# SCH_LeftHalf_2022-04-16.net
KiCad netlist of a schematic drawn in EasyEDA
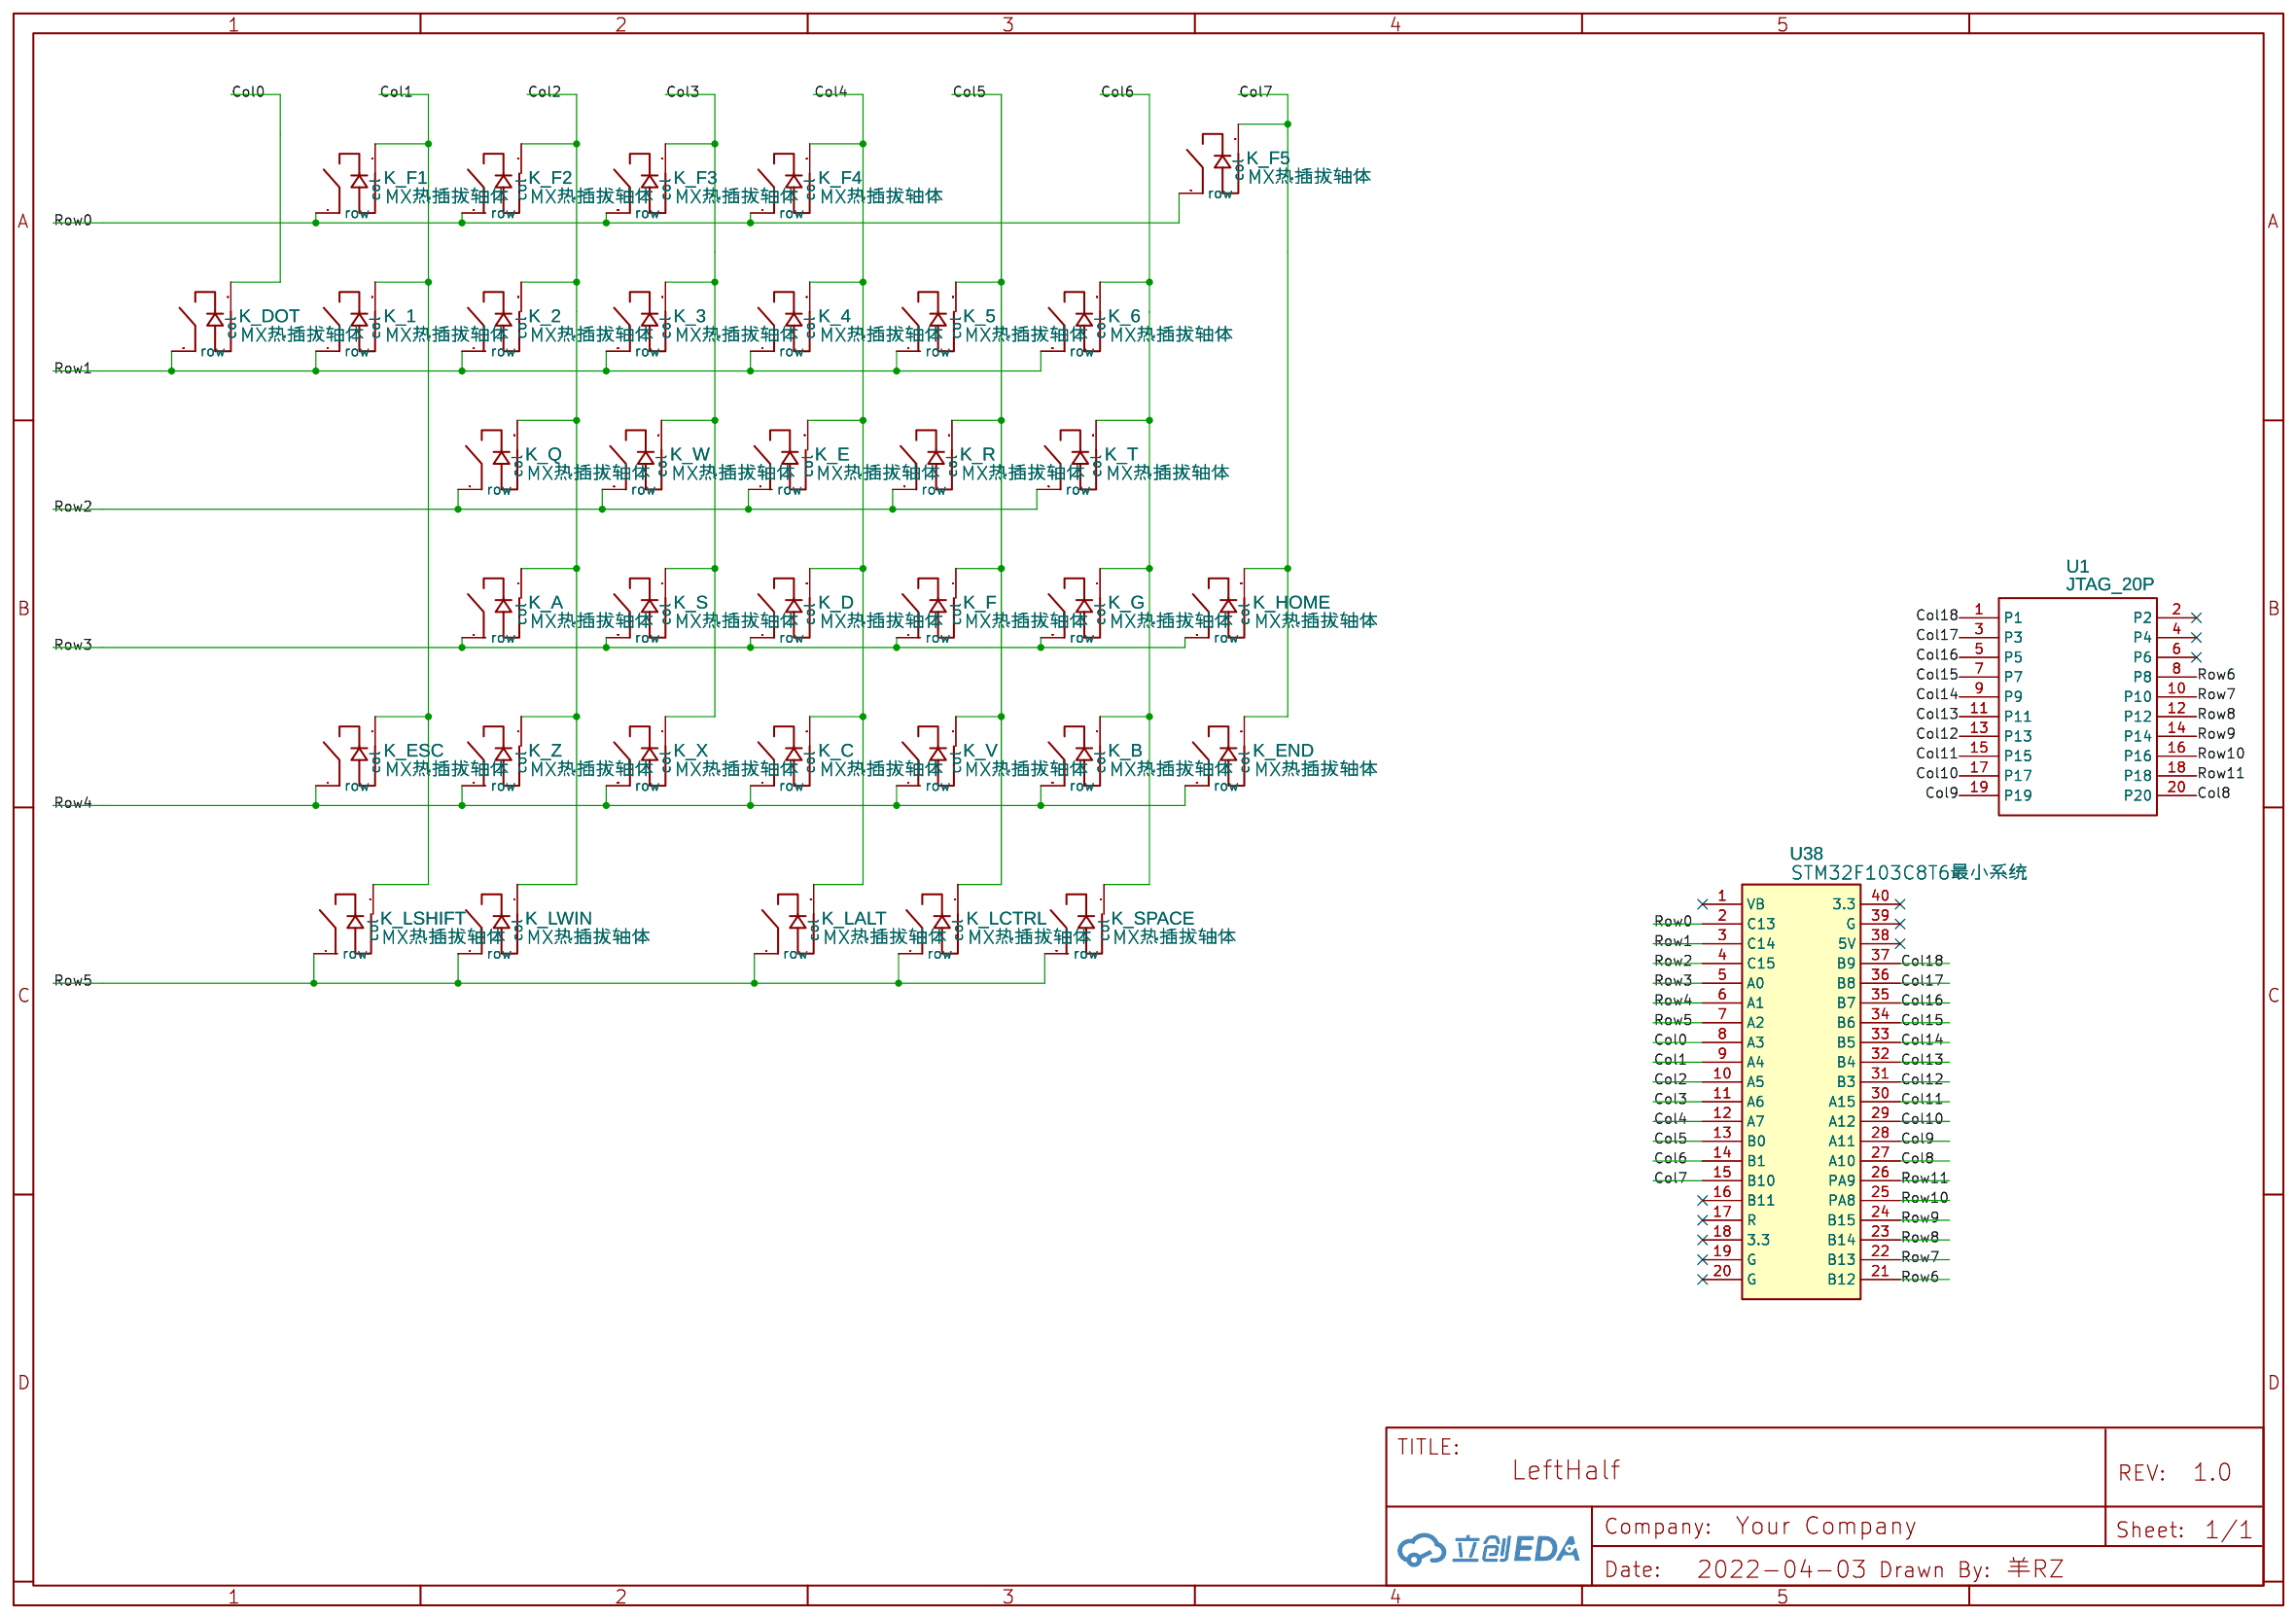
[diagram p0: schematic sheet]

(export (version "E")
  (design (tool "Eeschema 10.0.6"))
  (components
    (comp (ref "K_1") (value "MX热插拔轴体") (libsource (lib "") (part "MX热插拔轴体_6")))
    (comp (ref "K_2") (value "MX热插拔轴体") (libsource (lib "") (part "MX热插拔轴体_16")))
    (comp (ref "K_3") (value "MX热插拔轴体") (libsource (lib "") (part "MX热插拔轴体_6")))
    (comp (ref "K_4") (value "MX热插拔轴体") (libsource (lib "") (part "MX热插拔轴体_6")))
    (comp (ref "K_5") (value "MX热插拔轴体") (libsource (lib "") (part "MX热插拔轴体_16")))
    (comp (ref "K_6") (value "MX热插拔轴体") (libsource (lib "") (part "MX热插拔轴体_6")))
    (comp (ref "K_A") (value "MX热插拔轴体") (libsource (lib "") (part "MX热插拔轴体_11")))
    (comp (ref "K_B") (value "MX热插拔轴体") (libsource (lib "") (part "MX热插拔轴体_1")))
    (comp (ref "K_C") (value "MX热插拔轴体") (libsource (lib "") (part "MX热插拔轴体_20")))
    (comp (ref "K_D") (value "MX热插拔轴体") (libsource (lib "") (part "MX热插拔轴体_22")))
    (comp (ref "K_DOT") (value "MX热插拔轴体") (libsource (lib "") (part "MX热插拔轴体_17")))
    (comp (ref "K_E") (value "MX热插拔轴体") (libsource (lib "") (part "MX热插拔轴体_15")))
    (comp (ref "K_END") (value "MX热插拔轴体") (libsource (lib "") (part "MX热插拔轴体_10")))
    (comp (ref "K_ESC") (value "MX热插拔轴体") (libsource (lib "") (part "MX热插拔轴体_5")))
    (comp (ref "K_F") (value "MX热插拔轴体") (libsource (lib "") (part "MX热插拔轴体_12")))
    (comp (ref "K_F1") (value "MX热插拔轴体") (libsource (lib "") (part "MX热插拔轴体_2")))
    (comp (ref "K_F2") (value "MX热插拔轴体") (libsource (lib "") (part "MX热插拔轴体_12")))
    (comp (ref "K_F3") (value "MX热插拔轴体") (libsource (lib "") (part "MX热插拔轴体_2")))
    (comp (ref "K_F4") (value "MX热插拔轴体") (libsource (lib "") (part "MX热插拔轴体_2")))
    (comp (ref "K_F5") (value "MX热插拔轴体") (libsource (lib "") (part "MX热插拔轴体_2")))
    (comp (ref "K_G") (value "MX热插拔轴体") (libsource (lib "") (part "MX热插拔轴体_24")))
    (comp (ref "K_HOME") (value "MX热插拔轴体") (libsource (lib "") (part "MX热插拔轴体_26")))
    (comp (ref "K_LALT") (value "MX热插拔轴体") (libsource (lib "") (part "MX热插拔轴体_21")))
    (comp (ref "K_LCTRL") (value "MX热插拔轴体") (libsource (lib "") (part "MX热插拔轴体_8")))
    (comp (ref "K_LSHIFT") (value "MX热插拔轴体") (libsource (lib "") (part "MX热插拔轴体")))
    (comp (ref "K_LWIN") (value "MX热插拔轴体") (libsource (lib "") (part "MX热插拔轴体_23")))
    (comp (ref "K_Q") (value "MX热插拔轴体") (libsource (lib "") (part "MX热插拔轴体_19")))
    (comp (ref "K_R") (value "MX热插拔轴体") (libsource (lib "") (part "MX热插拔轴体_13")))
    (comp (ref "K_S") (value "MX热插拔轴体") (libsource (lib "") (part "MX热插拔轴体_4")))
    (comp (ref "K_SPACE") (value "MX热插拔轴体") (libsource (lib "") (part "MX热插拔轴体_14")))
    (comp (ref "K_T") (value "MX热插拔轴体") (libsource (lib "") (part "MX热插拔轴体_9")))
    (comp (ref "K_V") (value "MX热插拔轴体") (libsource (lib "") (part "MX热插拔轴体_18")))
    (comp (ref "K_W") (value "MX热插拔轴体") (libsource (lib "") (part "MX热插拔轴体_7")))
    (comp (ref "K_X") (value "MX热插拔轴体") (libsource (lib "") (part "MX热插拔轴体_25")))
    (comp (ref "K_Z") (value "MX热插拔轴体") (libsource (lib "") (part "MX热插拔轴体_3")))
    (comp (ref "U1") (value "JTAG_20P") (libsource (lib "") (part "JTAG_20P")))
    (comp (ref "U38")
      (value "STM32F103C8T6最小系统")
      (fields (field (name "BOM_Manufacturer Part") "New SchematicLib"))
      (libsource (lib "") (part "STM32F103C8T6最小系统"))
    )
  )
  (nets
    (net (code "1") (name "/Col0") (class "Default")
      (node (ref "K_DOT") (pin "COL") (pinfunction "col_COL") (pintype "unspecified"))
      (node (ref "U38") (pin "8") (pinfunction "A3_8") (pintype "bidirectional"))
    )
    (net (code "2") (name "/Col1") (class "Default")
      (node (ref "K_1") (pin "COL") (pinfunction "col_COL") (pintype "unspecified"))
      (node (ref "K_ESC") (pin "COL") (pinfunction "col_COL") (pintype "unspecified"))
      (node (ref "K_F1") (pin "COL") (pinfunction "col_COL") (pintype "unspecified"))
      (node (ref "K_LSHIFT") (pin "COL") (pinfunction "col_COL") (pintype "unspecified"))
      (node (ref "U38") (pin "9") (pinfunction "A4_9") (pintype "bidirectional"))
    )
    (net (code "3") (name "/Col2") (class "Default")
      (node (ref "K_2") (pin "COL") (pinfunction "col_COL") (pintype "unspecified"))
      (node (ref "K_A") (pin "COL") (pinfunction "col_COL") (pintype "unspecified"))
      (node (ref "K_F2") (pin "COL") (pinfunction "col_COL") (pintype "unspecified"))
      (node (ref "K_LWIN") (pin "COL") (pinfunction "col_COL") (pintype "unspecified"))
      (node (ref "K_Q") (pin "COL") (pinfunction "col_COL") (pintype "unspecified"))
      (node (ref "K_Z") (pin "COL") (pinfunction "col_COL") (pintype "unspecified"))
      (node (ref "U38") (pin "10") (pinfunction "A5_10") (pintype "bidirectional"))
    )
    (net (code "4") (name "/Col3") (class "Default")
      (node (ref "K_3") (pin "COL") (pinfunction "col_COL") (pintype "unspecified"))
      (node (ref "K_F3") (pin "COL") (pinfunction "col_COL") (pintype "unspecified"))
      (node (ref "K_S") (pin "COL") (pinfunction "col_COL") (pintype "unspecified"))
      (node (ref "K_W") (pin "COL") (pinfunction "col_COL") (pintype "unspecified"))
      (node (ref "K_X") (pin "COL") (pinfunction "col_COL") (pintype "unspecified"))
      (node (ref "U38") (pin "11") (pinfunction "A6_11") (pintype "bidirectional"))
    )
    (net (code "5") (name "/Col4") (class "Default")
      (node (ref "K_4") (pin "COL") (pinfunction "col_COL") (pintype "unspecified"))
      (node (ref "K_C") (pin "COL") (pinfunction "col_COL") (pintype "unspecified"))
      (node (ref "K_D") (pin "COL") (pinfunction "col_COL") (pintype "unspecified"))
      (node (ref "K_E") (pin "COL") (pinfunction "col_COL") (pintype "unspecified"))
      (node (ref "K_F4") (pin "COL") (pinfunction "col_COL") (pintype "unspecified"))
      (node (ref "K_LALT") (pin "COL") (pinfunction "col_COL") (pintype "unspecified"))
      (node (ref "U38") (pin "12") (pinfunction "A7_12") (pintype "bidirectional"))
    )
    (net (code "6") (name "/Col5") (class "Default")
      (node (ref "K_5") (pin "COL") (pinfunction "col_COL") (pintype "unspecified"))
      (node (ref "K_F") (pin "COL") (pinfunction "col_COL") (pintype "unspecified"))
      (node (ref "K_LCTRL") (pin "COL") (pinfunction "col_COL") (pintype "unspecified"))
      (node (ref "K_R") (pin "COL") (pinfunction "col_COL") (pintype "unspecified"))
      (node (ref "K_V") (pin "COL") (pinfunction "col_COL") (pintype "unspecified"))
      (node (ref "U38") (pin "13") (pinfunction "B0_13") (pintype "bidirectional"))
    )
    (net (code "7") (name "/Col6") (class "Default")
      (node (ref "K_6") (pin "COL") (pinfunction "col_COL") (pintype "unspecified"))
      (node (ref "K_B") (pin "COL") (pinfunction "col_COL") (pintype "unspecified"))
      (node (ref "K_G") (pin "COL") (pinfunction "col_COL") (pintype "unspecified"))
      (node (ref "K_SPACE") (pin "COL") (pinfunction "col_COL") (pintype "unspecified"))
      (node (ref "K_T") (pin "COL") (pinfunction "col_COL") (pintype "unspecified"))
      (node (ref "U38") (pin "14") (pinfunction "B1_14") (pintype "bidirectional"))
    )
    (net (code "8") (name "/Col7") (class "Default")
      (node (ref "K_END") (pin "COL") (pinfunction "col_COL") (pintype "unspecified"))
      (node (ref "K_F5") (pin "COL") (pinfunction "col_COL") (pintype "unspecified"))
      (node (ref "K_HOME") (pin "COL") (pinfunction "col_COL") (pintype "unspecified"))
      (node (ref "U38") (pin "15") (pinfunction "B10_15") (pintype "bidirectional"))
    )
    (net (code "9") (name "/Col8") (class "Default")
      (node (ref "U1") (pin "20") (pinfunction "P20_20") (pintype "unspecified"))
      (node (ref "U38") (pin "27") (pinfunction "A10_27") (pintype "bidirectional"))
    )
    (net (code "10") (name "/Col9") (class "Default")
      (node (ref "U1") (pin "19") (pinfunction "P19_19") (pintype "unspecified"))
      (node (ref "U38") (pin "28") (pinfunction "A11_28") (pintype "bidirectional"))
    )
    (net (code "11") (name "/Col10") (class "Default")
      (node (ref "U1") (pin "17") (pinfunction "P17_17") (pintype "unspecified"))
      (node (ref "U38") (pin "29") (pinfunction "A12_29") (pintype "bidirectional"))
    )
    (net (code "12") (name "/Col11") (class "Default")
      (node (ref "U1") (pin "15") (pinfunction "P15_15") (pintype "unspecified"))
      (node (ref "U38") (pin "30") (pinfunction "A15_30") (pintype "bidirectional"))
    )
    (net (code "13") (name "/Col12") (class "Default")
      (node (ref "U1") (pin "13") (pinfunction "P13_13") (pintype "unspecified"))
      (node (ref "U38") (pin "31") (pinfunction "B3_31") (pintype "bidirectional"))
    )
    (net (code "14") (name "/Col13") (class "Default")
      (node (ref "U1") (pin "11") (pinfunction "P11_11") (pintype "unspecified"))
      (node (ref "U38") (pin "32") (pinfunction "B4_32") (pintype "bidirectional"))
    )
    (net (code "15") (name "/Col14") (class "Default")
      (node (ref "U1") (pin "9") (pinfunction "P9_9") (pintype "unspecified"))
      (node (ref "U38") (pin "33") (pinfunction "B5_33") (pintype "bidirectional"))
    )
    (net (code "16") (name "/Col15") (class "Default")
      (node (ref "U1") (pin "7") (pinfunction "P7_7") (pintype "unspecified"))
      (node (ref "U38") (pin "34") (pinfunction "B6_34") (pintype "bidirectional"))
    )
    (net (code "17") (name "/Col16") (class "Default")
      (node (ref "U1") (pin "5") (pinfunction "P5_5") (pintype "unspecified"))
      (node (ref "U38") (pin "35") (pinfunction "B7_35") (pintype "bidirectional"))
    )
    (net (code "18") (name "/Col17") (class "Default")
      (node (ref "U1") (pin "3") (pinfunction "P3_3") (pintype "unspecified"))
      (node (ref "U38") (pin "36") (pinfunction "B8_36") (pintype "bidirectional"))
    )
    (net (code "19") (name "/Col18") (class "Default")
      (node (ref "U1") (pin "1") (pinfunction "P1_1") (pintype "unspecified"))
      (node (ref "U38") (pin "37") (pinfunction "B9_37") (pintype "bidirectional"))
    )
    (net (code "20") (name "/Row0") (class "Default")
      (node (ref "K_F1") (pin "ROW") (pinfunction "row_ROW") (pintype "unspecified"))
      (node (ref "K_F2") (pin "ROW") (pinfunction "row_ROW") (pintype "unspecified"))
      (node (ref "K_F3") (pin "ROW") (pinfunction "row_ROW") (pintype "unspecified"))
      (node (ref "K_F4") (pin "ROW") (pinfunction "row_ROW") (pintype "unspecified"))
      (node (ref "K_F5") (pin "ROW") (pinfunction "row_ROW") (pintype "unspecified"))
      (node (ref "U38") (pin "2") (pinfunction "C13_2") (pintype "bidirectional"))
    )
    (net (code "21") (name "/Row1") (class "Default")
      (node (ref "K_1") (pin "ROW") (pinfunction "row_ROW") (pintype "unspecified"))
      (node (ref "K_2") (pin "ROW") (pinfunction "row_ROW") (pintype "unspecified"))
      (node (ref "K_3") (pin "ROW") (pinfunction "row_ROW") (pintype "unspecified"))
      (node (ref "K_4") (pin "ROW") (pinfunction "row_ROW") (pintype "unspecified"))
      (node (ref "K_5") (pin "ROW") (pinfunction "row_ROW") (pintype "unspecified"))
      (node (ref "K_6") (pin "ROW") (pinfunction "row_ROW") (pintype "unspecified"))
      (node (ref "K_DOT") (pin "ROW") (pinfunction "row_ROW") (pintype "unspecified"))
      (node (ref "U38") (pin "3") (pinfunction "C14_3") (pintype "bidirectional"))
    )
    (net (code "22") (name "/Row2") (class "Default")
      (node (ref "K_E") (pin "ROW") (pinfunction "row_ROW") (pintype "unspecified"))
      (node (ref "K_Q") (pin "ROW") (pinfunction "row_ROW") (pintype "unspecified"))
      (node (ref "K_R") (pin "ROW") (pinfunction "row_ROW") (pintype "unspecified"))
      (node (ref "K_T") (pin "ROW") (pinfunction "row_ROW") (pintype "unspecified"))
      (node (ref "K_W") (pin "ROW") (pinfunction "row_ROW") (pintype "unspecified"))
      (node (ref "U38") (pin "4") (pinfunction "C15_4") (pintype "bidirectional"))
    )
    (net (code "23") (name "/Row3") (class "Default")
      (node (ref "K_A") (pin "ROW") (pinfunction "row_ROW") (pintype "unspecified"))
      (node (ref "K_D") (pin "ROW") (pinfunction "row_ROW") (pintype "unspecified"))
      (node (ref "K_F") (pin "ROW") (pinfunction "row_ROW") (pintype "unspecified"))
      (node (ref "K_G") (pin "ROW") (pinfunction "row_ROW") (pintype "unspecified"))
      (node (ref "K_HOME") (pin "ROW") (pinfunction "row_ROW") (pintype "unspecified"))
      (node (ref "K_S") (pin "ROW") (pinfunction "row_ROW") (pintype "unspecified"))
      (node (ref "U38") (pin "5") (pinfunction "A0_5") (pintype "bidirectional"))
    )
    (net (code "24") (name "/Row4") (class "Default")
      (node (ref "K_B") (pin "ROW") (pinfunction "row_ROW") (pintype "unspecified"))
      (node (ref "K_C") (pin "ROW") (pinfunction "row_ROW") (pintype "unspecified"))
      (node (ref "K_END") (pin "ROW") (pinfunction "row_ROW") (pintype "unspecified"))
      (node (ref "K_ESC") (pin "ROW") (pinfunction "row_ROW") (pintype "unspecified"))
      (node (ref "K_V") (pin "ROW") (pinfunction "row_ROW") (pintype "unspecified"))
      (node (ref "K_X") (pin "ROW") (pinfunction "row_ROW") (pintype "unspecified"))
      (node (ref "K_Z") (pin "ROW") (pinfunction "row_ROW") (pintype "unspecified"))
      (node (ref "U38") (pin "6") (pinfunction "A1_6") (pintype "bidirectional"))
    )
    (net (code "25") (name "/Row5") (class "Default")
      (node (ref "K_LALT") (pin "ROW") (pinfunction "row_ROW") (pintype "unspecified"))
      (node (ref "K_LCTRL") (pin "ROW") (pinfunction "row_ROW") (pintype "unspecified"))
      (node (ref "K_LSHIFT") (pin "ROW") (pinfunction "row_ROW") (pintype "unspecified"))
      (node (ref "K_LWIN") (pin "ROW") (pinfunction "row_ROW") (pintype "unspecified"))
      (node (ref "K_SPACE") (pin "ROW") (pinfunction "row_ROW") (pintype "unspecified"))
      (node (ref "U38") (pin "7") (pinfunction "A2_7") (pintype "bidirectional"))
    )
    (net (code "26") (name "/Row6") (class "Default")
      (node (ref "U1") (pin "8") (pinfunction "P8_8") (pintype "unspecified"))
      (node (ref "U38") (pin "21") (pinfunction "B12_21") (pintype "bidirectional"))
    )
    (net (code "27") (name "/Row7") (class "Default")
      (node (ref "U1") (pin "10") (pinfunction "P10_10") (pintype "unspecified"))
      (node (ref "U38") (pin "22") (pinfunction "B13_22") (pintype "bidirectional"))
    )
    (net (code "28") (name "/Row8") (class "Default")
      (node (ref "U1") (pin "12") (pinfunction "P12_12") (pintype "unspecified"))
      (node (ref "U38") (pin "23") (pinfunction "B14_23") (pintype "bidirectional"))
    )
    (net (code "29") (name "/Row9") (class "Default")
      (node (ref "U1") (pin "14") (pinfunction "P14_14") (pintype "unspecified"))
      (node (ref "U38") (pin "24") (pinfunction "B15_24") (pintype "bidirectional"))
    )
    (net (code "30") (name "/Row10") (class "Default")
      (node (ref "U1") (pin "16") (pinfunction "P16_16") (pintype "unspecified"))
      (node (ref "U38") (pin "25") (pinfunction "PA8_25") (pintype "bidirectional"))
    )
    (net (code "31") (name "/Row11") (class "Default")
      (node (ref "U1") (pin "18") (pinfunction "P18_18") (pintype "unspecified"))
      (node (ref "U38") (pin "26") (pinfunction "PA9_26") (pintype "bidirectional"))
    )
    (net (code "32") (name "unconnected-(U1-P2-Pad2)") (class "Default")
      (node (ref "U1") (pin "2") (pinfunction "P2_2") (pintype "unspecified+no_connect"))
    )
    (net (code "33") (name "unconnected-(U1-P4-Pad4)") (class "Default")
      (node (ref "U1") (pin "4") (pinfunction "P4_4") (pintype "unspecified+no_connect"))
    )
    (net (code "34") (name "unconnected-(U1-P6-Pad6)") (class "Default")
      (node (ref "U1") (pin "6") (pinfunction "P6_6") (pintype "unspecified+no_connect"))
    )
    (net (code "35") (name "unconnected-(U38-3.3-Pad18)") (class "Default")
      (node (ref "U38") (pin "18") (pinfunction "3.3_18") (pintype "bidirectional+no_connect"))
    )
    (net (code "36") (name "unconnected-(U38-3.3-Pad40)") (class "Default")
      (node (ref "U38") (pin "40") (pinfunction "3.3_40") (pintype "unspecified+no_connect"))
    )
    (net (code "37") (name "unconnected-(U38-5V-Pad38)") (class "Default")
      (node (ref "U38") (pin "38") (pinfunction "5V_38") (pintype "unspecified+no_connect"))
    )
    (net (code "38") (name "unconnected-(U38-B11-Pad16)") (class "Default")
      (node (ref "U38") (pin "16") (pinfunction "B11_16") (pintype "bidirectional+no_connect"))
    )
    (net (code "39") (name "unconnected-(U38-G-Pad19)") (class "Default")
      (node (ref "U38") (pin "19") (pinfunction "G_19") (pintype "bidirectional+no_connect"))
    )
    (net (code "40") (name "unconnected-(U38-G-Pad20)") (class "Default")
      (node (ref "U38") (pin "20") (pinfunction "G_20") (pintype "bidirectional+no_connect"))
    )
    (net (code "41") (name "unconnected-(U38-G-Pad39)") (class "Default")
      (node (ref "U38") (pin "39") (pinfunction "G_39") (pintype "unspecified+no_connect"))
    )
    (net (code "42") (name "unconnected-(U38-R-Pad17)") (class "Default")
      (node (ref "U38") (pin "17") (pinfunction "R_17") (pintype "bidirectional+no_connect"))
    )
    (net (code "43") (name "unconnected-(U38-VB-Pad1)") (class "Default")
      (node (ref "U38") (pin "1") (pinfunction "VB_1") (pintype "unspecified+no_connect"))
    )
  )
)
